# DC-Motor-DRV.net
KiCad netlist of a schematic drawn in Altium Designer
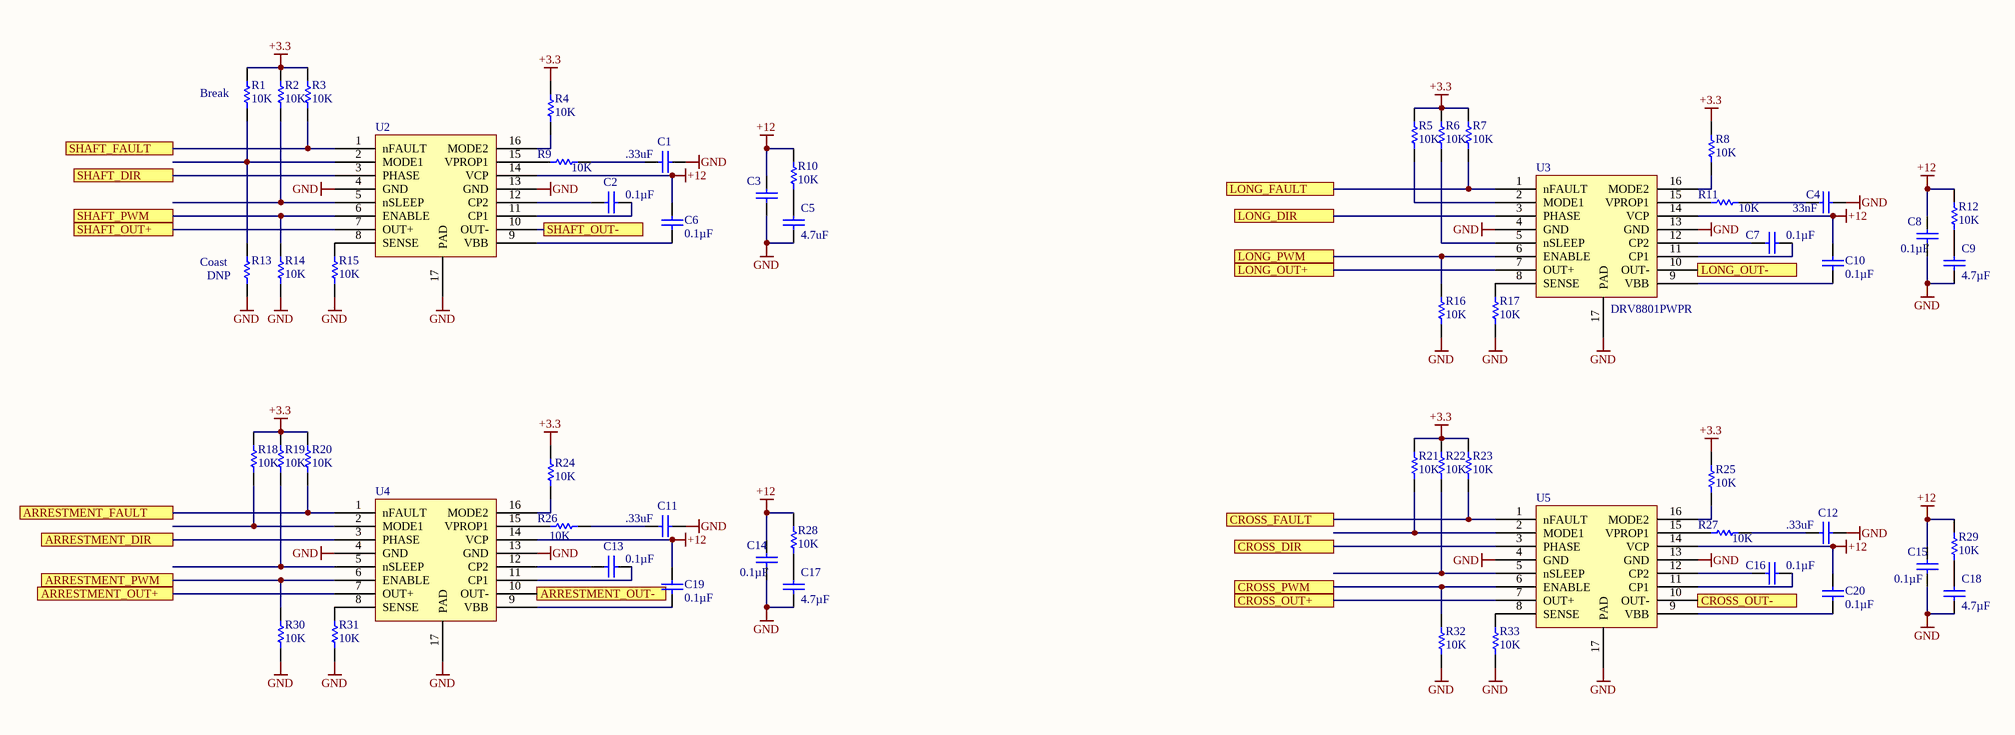
[diagram p0: DC-Motor-DRV.SchDoc]

(export (version "E")
  (design (tool "Eeschema 10.0.6"))
  (components
    (comp (ref "C1")
      (value ".33uF")
      (footprint "CAPC0805(2012)145_N")
      (description "CAP CER 0.1UF 25V X7R 0805")
      (fields
        (field (name "MANUFACTURER") "Wurth Electronics Inc.")
        (field (name "MANUFACTURER PART NUMBER") "885012207069")
      )
      (libsource (lib "Altium Content Vault") (part "CMP-1036-04795-1"))
    )
    (comp (ref "C2")
      (value "0.1uF")
      (footprint "CAPC0805(2012)145_N")
      (description "CAP CER 0.1UF 25V X7R 0805")
      (fields
        (field (name "MANUFACTURER") "Murata Electronics North America")
        (field (name "MANUFACTURER PART NUMBER") "GRM21BR71E104KA01L")
        (field (name "CAPACITANCE") "0.1µF")
      )
      (libsource (lib "Altium Content Vault") (part "CMP-1036-04795-1"))
    )
    (comp (ref "C3")
      (value "0.1uF")
      (footprint "CAPC0805(2012)145_N")
      (description "CAP CER 0.1UF 25V X7R 0805")
      (fields
        (field (name "MANUFACTURER") "Murata Electronics North America")
        (field (name "MANUFACTURER PART NUMBER") "GRM21BR71E104KA01L")
      )
      (libsource (lib "Altium Content Vault") (part "CMP-1036-04795-1"))
    )
    (comp (ref "C4")
      (value "33nF")
      (footprint "CAPC0402(1005)60_L")
      (description "CAP CER 33UF 10V X7R 0402")
      (fields
        (field (name "MANUFACTURER") "Murata Electronics North America")
        (field (name "MANUFACTURER PART NUMBER") "GRM155R71A104KA01D")
      )
      (libsource (lib "Altium Content Vault") (part "CMP-1034-00252-1"))
    )
    (comp (ref "C5")
      (value "4.7uF")
      (footprint "CAPC0805(2012)145_N")
      (description "CAP CER 4.7UF 25V 10% X7R 0805")
      (fields
        (field (name "MANUFACTURER") "Murata Electronics North America")
        (field (name "MANUFACTURER PART NUMBER") "GRM21BR71E104KA01L")
      )
      (libsource (lib "Altium Content Vault") (part "CMP-1036-04795-1"))
    )
    (comp (ref "C6")
      (value "0.1uF")
      (footprint "CAPC0805(2012)145_N")
      (description "CAP CER 0.1UF 25V X7R 0805")
      (fields
        (field (name "MANUFACTURER") "Murata Electronics North America")
        (field (name "MANUFACTURER PART NUMBER") "GRM21BR71E104KA01L")
        (field (name "CAPACITANCE") "0.1µF")
      )
      (libsource (lib "Altium Content Vault") (part "CMP-1036-04795-1"))
    )
    (comp (ref "C7")
      (value "0.1uF")
      (footprint "CAPC0805(2012)145_N")
      (description "CAP CER 0.1UF 25V X7R 0805")
      (fields
        (field (name "MANUFACTURER") "Murata Electronics North America")
        (field (name "MANUFACTURER PART NUMBER") "GRM21BR71E104KA01L")
        (field (name "CAPACITANCE") "0.1µF")
      )
      (libsource (lib "Altium Content Vault") (part "CMP-1036-04795-1"))
    )
    (comp (ref "C8")
      (value ".1uF")
      (footprint "CAPC0805(2012)145_N")
      (description "CAP CER 0.1UF 25V X7R 0805")
      (fields
        (field (name "MANUFACTURER") "Murata Electronics North America")
        (field (name "MANUFACTURER PART NUMBER") "GRM21BR71E104KA01L")
        (field (name "CAPACITANCE") "0.1µF")
      )
      (libsource (lib "Altium Content Vault") (part "CMP-1036-04795-1"))
    )
    (comp (ref "C9")
      (value "4.7uF")
      (footprint "CAPC0805(2012)145_N")
      (description "CAP CER 4.7UF 25V X7R 0805")
      (fields
        (field (name "MANUFACTURER") "Murata Electronics North America")
        (field (name "MANUFACTURER PART NUMBER") "GRM21BR71E104KA01L")
        (field (name "CAPACITANCE") "4.7µF")
      )
      (libsource (lib "Altium Content Vault") (part "CMP-1036-04795-1"))
    )
    (comp (ref "C10")
      (value ".1uF")
      (footprint "CAPC0805(2012)145_N")
      (description "CAP CER 0.1UF 25V X7R 0805")
      (fields
        (field (name "MANUFACTURER") "Murata Electronics North America")
        (field (name "MANUFACTURER PART NUMBER") "GRM21BR71E104KA01L")
        (field (name "CAPACITANCE") "0.1µF")
      )
      (libsource (lib "Altium Content Vault") (part "CMP-1036-04795-1"))
    )
    (comp (ref "C11")
      (value ".33uF")
      (footprint "CAPC0805(2012)145_N")
      (description "CAP CER 0.1UF 25V X7R 0805")
      (fields
        (field (name "MANUFACTURER") "Wurth Electronics Inc.")
        (field (name "MANUFACTURER PART NUMBER") "885012207069")
      )
      (libsource (lib "Altium Content Vault") (part "CMP-1036-04795-1"))
    )
    (comp (ref "C12")
      (value ".33uF")
      (footprint "CAPC0805(2012)145_N")
      (description "CAP CER 0.1UF 25V X7R 0805")
      (fields
        (field (name "MANUFACTURER") "Wurth Electronics Inc.")
        (field (name "MANUFACTURER PART NUMBER") "885012207069")
      )
      (libsource (lib "Altium Content Vault") (part "CMP-1036-04795-1"))
    )
    (comp (ref "C13")
      (value "CAP CER 0.1UF 25V X7R 0805")
      (footprint "CAPC0805(2012)145_N")
      (fields
        (field (name "MANUFACTURER") "Murata Electronics North America")
        (field (name "MANUFACTURER PART NUMBER") "GRM21BR71E104KA01L")
        (field (name "CAPACITANCE") "0.1µF")
        (field (name "TOLERANCE") "±10%")
      )
      (libsource (lib "Altium Content Vault") (part "CMP-1036-04795-1"))
    )
    (comp (ref "C14")
      (value "CAP CER 0.1UF 25V X7R 0805")
      (footprint "CAPC0805(2012)145_N")
      (fields
        (field (name "MANUFACTURER") "Murata Electronics North America")
        (field (name "MANUFACTURER PART NUMBER") "GRM21BR71E104KA01L")
        (field (name "CAPACITANCE") "0.1µF")
        (field (name "TOLERANCE") "±10%")
      )
      (libsource (lib "Altium Content Vault") (part "CMP-1036-04795-1"))
    )
    (comp (ref "C15")
      (value "0.1uF")
      (footprint "CAPC0805(2012)145_N")
      (description "CAP CER 0.1UF 25V X7R 0805")
      (fields
        (field (name "MANUFACTURER") "Murata Electronics North America")
        (field (name "MANUFACTURER PART NUMBER") "GRM21BR71E104KA01L")
        (field (name "CAPACITANCE") "0.1µF")
      )
      (libsource (lib "Altium Content Vault") (part "CMP-1036-04795-1"))
    )
    (comp (ref "C16")
      (value "0.1uF")
      (footprint "CAPC0805(2012)145_N")
      (description "CAP CER 0.1UF 25V X7R 0805")
      (fields
        (field (name "MANUFACTURER") "Murata Electronics North America")
        (field (name "MANUFACTURER PART NUMBER") "GRM21BR71E104KA01L")
        (field (name "CAPACITANCE") "0.1µF")
      )
      (libsource (lib "Altium Content Vault") (part "CMP-1036-04795-1"))
    )
    (comp (ref "C17")
      (value "CAP CER 0.1UF 25V X7R 0805")
      (footprint "CAPC0805(2012)145_N")
      (description "CAP CER 0.47UF 25V X7R 0805")
      (fields
        (field (name "MANUFACTURER") "Murata Electronics North America")
        (field (name "MANUFACTURER PART NUMBER") "GRM21BR71E104KA01L")
        (field (name "CAPACITANCE") "4.7µF")
      )
      (libsource (lib "Altium Content Vault") (part "CMP-1036-04795-1"))
    )
    (comp (ref "C18")
      (value "4.7uF")
      (footprint "CAPC0805(2012)145_N")
      (description "CAP CER 4.7UF 25V X7R 0805")
      (fields
        (field (name "MANUFACTURER") "Murata Electronics North America")
        (field (name "MANUFACTURER PART NUMBER") "GRM21BR71E104KA01L")
        (field (name "CAPACITANCE") "4.7µF")
      )
      (libsource (lib "Altium Content Vault") (part "CMP-1036-04795-1"))
    )
    (comp (ref "C19")
      (value "CAP CER 0.1UF 25V X7R 0805")
      (footprint "CAPC0805(2012)145_N")
      (fields
        (field (name "MANUFACTURER") "Murata Electronics North America")
        (field (name "MANUFACTURER PART NUMBER") "GRM21BR71E104KA01L")
        (field (name "CAPACITANCE") "0.1µF")
        (field (name "TOLERANCE") "±10%")
      )
      (libsource (lib "Altium Content Vault") (part "CMP-1036-04795-1"))
    )
    (comp (ref "C20")
      (value "0.1uF")
      (footprint "CAPC0805(2012)145_N")
      (description "CAP CER 0.1UF 25V X7R 0805")
      (fields
        (field (name "MANUFACTURER") "Murata Electronics North America")
        (field (name "MANUFACTURER PART NUMBER") "GRM21BR71E104KA01L")
        (field (name "CAPACITANCE") "0.1µF")
      )
      (libsource (lib "Altium Content Vault") (part "CMP-1036-04795-1"))
    )
    (comp (ref "R1")
      (value "10K")
      (footprint "RESC0805(2012)_L")
      (description "RES SMD 10K OHM 1% 1/8W 0805")
      (fields
        (field (name "MANUFACTURER") "Vishay Dale")
        (field (name "MANUFACTURER PART NUMBER") "CRCW080510K0FKEA")
      )
      (libsource (lib "Altium Content Vault") (part "CMP-1013-00215-1"))
    )
    (comp (ref "R2")
      (value "10K")
      (footprint "RESC0805(2012)_L")
      (description "RES SMD 10K OHM 1% 1/8W 0805")
      (fields
        (field (name "MANUFACTURER") "Vishay Dale")
        (field (name "MANUFACTURER PART NUMBER") "CRCW080510K0FKEA")
      )
      (libsource (lib "Altium Content Vault") (part "CMP-1013-00215-1"))
    )
    (comp (ref "R3")
      (value "10K")
      (footprint "RESC0805(2012)_L")
      (description "RES SMD 10K OHM 1% 1/8W 0805")
      (fields
        (field (name "MANUFACTURER") "Vishay Dale")
        (field (name "MANUFACTURER PART NUMBER") "CRCW080510K0FKEA")
      )
      (libsource (lib "Altium Content Vault") (part "CMP-1013-00215-1"))
    )
    (comp (ref "R4")
      (value "10K")
      (footprint "RESC0805(2012)_L")
      (description "RES SMD 10K OHM 1% 1/8W 0805")
      (fields
        (field (name "MANUFACTURER") "Vishay Dale")
        (field (name "MANUFACTURER PART NUMBER") "CRCW080510K0FKEA")
      )
      (libsource (lib "Altium Content Vault") (part "CMP-1013-00215-1"))
    )
    (comp (ref "R5")
      (value "10K")
      (footprint "RESC0805(2012)_L")
      (description "RES SMD 10K OHM 1% 1/8W 0805")
      (fields
        (field (name "MANUFACTURER") "Vishay Dale")
        (field (name "MANUFACTURER PART NUMBER") "CRCW080510K0FKEA")
      )
      (libsource (lib "Altium Content Vault") (part "CMP-1013-00215-1"))
    )
    (comp (ref "R6")
      (value "10K")
      (footprint "RESC0805(2012)_L")
      (description "RES SMD 10K OHM 1% 1/8W 0805")
      (fields
        (field (name "MANUFACTURER") "Vishay Dale")
        (field (name "MANUFACTURER PART NUMBER") "CRCW080510K0FKEA")
      )
      (libsource (lib "Altium Content Vault") (part "CMP-1013-00215-1"))
    )
    (comp (ref "R7")
      (value "10K")
      (footprint "RESC0805(2012)_L")
      (description "RES SMD 10K OHM 1% 1/8W 0805")
      (fields
        (field (name "MANUFACTURER") "Vishay Dale")
        (field (name "MANUFACTURER PART NUMBER") "CRCW080510K0FKEA")
      )
      (libsource (lib "Altium Content Vault") (part "CMP-1013-00215-1"))
    )
    (comp (ref "R8")
      (value "10K")
      (footprint "RESC0805(2012)_L")
      (description "RES SMD 10K OHM 1% 1/8W 0805")
      (fields
        (field (name "MANUFACTURER") "Vishay Dale")
        (field (name "MANUFACTURER PART NUMBER") "CRCW080510K0FKEA")
      )
      (libsource (lib "Altium Content Vault") (part "CMP-1013-00215-1"))
    )
    (comp (ref "R9")
      (value "10K")
      (footprint "RESC0805(2012)_L")
      (description "RES SMD 10K OHM 1% 1/8W 0805")
      (fields
        (field (name "MANUFACTURER") "Vishay Dale")
        (field (name "MANUFACTURER PART NUMBER") "CRCW080510K0FKEA")
      )
      (libsource (lib "Altium Content Vault") (part "CMP-1013-00215-1"))
    )
    (comp (ref "R10")
      (value "10K")
      (footprint "RESC0805(2012)_L")
      (description "RES SMD 1R OHM 1% 1/8W 0805")
      (fields
        (field (name "MANUFACTURER") "Vishay Dale")
        (field (name "MANUFACTURER PART NUMBER") "CRCW080510K0FKEA")
      )
      (libsource (lib "Altium Content Vault") (part "CMP-1013-00215-1"))
    )
    (comp (ref "R11")
      (value "10K")
      (footprint "RESC0805(2012)_L")
      (description "RES SMD 10K OHM 1% 1/8W 0805")
      (fields
        (field (name "MANUFACTURER") "Vishay Dale")
        (field (name "MANUFACTURER PART NUMBER") "CRCW080510K0FKEA")
      )
      (libsource (lib "Altium Content Vault") (part "CMP-1013-00215-1"))
    )
    (comp (ref "R12")
      (value "10K")
      (footprint "RESC0805(2012)_L")
      (description "RES SMD 1R OHM 1% 1/8W 0805")
      (fields
        (field (name "MANUFACTURER") "Vishay Dale")
        (field (name "MANUFACTURER PART NUMBER") "CRCW080510K0FKEA")
      )
      (libsource (lib "Altium Content Vault") (part "CMP-1013-00215-1"))
    )
    (comp (ref "R13")
      (value "DNP")
      (footprint "RESC0805(2012)_L")
      (description "RES SMD 10K OHM 1% 1/8W 0805")
      (fields
        (field (name "MANUFACTURER") "Vishay Dale")
        (field (name "MANUFACTURER PART NUMBER") "CRCW080510K0FKEA")
      )
      (libsource (lib "Altium Content Vault") (part "CMP-1013-00215-1"))
    )
    (comp (ref "R14")
      (value "10K")
      (footprint "RESC0805(2012)_L")
      (description "RES SMD 10K OHM 1% 1/8W 0805")
      (fields
        (field (name "MANUFACTURER") "Vishay Dale")
        (field (name "MANUFACTURER PART NUMBER") "CRCW080510K0FKEA")
      )
      (libsource (lib "Altium Content Vault") (part "CMP-1013-00215-1"))
    )
    (comp (ref "R15")
      (value "10K")
      (footprint "RESC0805(2012)_L")
      (description "RES SMD 10K OHM 1% 1/8W 0805")
      (fields
        (field (name "MANUFACTURER") "Vishay Dale")
        (field (name "MANUFACTURER PART NUMBER") "CRCW080510K0FKEA")
      )
      (libsource (lib "Altium Content Vault") (part "CMP-1013-00215-1"))
    )
    (comp (ref "R16")
      (value "10K")
      (footprint "RESC0805(2012)_L")
      (description "RES SMD 10K OHM 1% 1/8W 0805")
      (fields
        (field (name "MANUFACTURER") "Vishay Dale")
        (field (name "MANUFACTURER PART NUMBER") "CRCW080510K0FKEA")
      )
      (libsource (lib "Altium Content Vault") (part "CMP-1013-00215-1"))
    )
    (comp (ref "R17")
      (value "10K")
      (footprint "RESC0805(2012)_L")
      (description "RES SMD 10K OHM 1% 1/8W 0805")
      (fields
        (field (name "MANUFACTURER") "Vishay Dale")
        (field (name "MANUFACTURER PART NUMBER") "CRCW080510K0FKEA")
      )
      (libsource (lib "Altium Content Vault") (part "CMP-1013-00215-1"))
    )
    (comp (ref "R18")
      (value "10K")
      (footprint "RESC0805(2012)_L")
      (description "RES SMD 10K OHM 1% 1/8W 0805")
      (fields
        (field (name "MANUFACTURER") "Vishay Dale")
        (field (name "MANUFACTURER PART NUMBER") "CRCW080510K0FKEA")
      )
      (libsource (lib "Altium Content Vault") (part "CMP-1013-00215-1"))
    )
    (comp (ref "R19")
      (value "10K")
      (footprint "RESC0805(2012)_L")
      (description "RES SMD 10K OHM 1% 1/8W 0805")
      (fields
        (field (name "MANUFACTURER") "Vishay Dale")
        (field (name "MANUFACTURER PART NUMBER") "CRCW080510K0FKEA")
      )
      (libsource (lib "Altium Content Vault") (part "CMP-1013-00215-1"))
    )
    (comp (ref "R20")
      (value "10K")
      (footprint "RESC0805(2012)_L")
      (description "RES SMD 10K OHM 1% 1/8W 0805")
      (fields
        (field (name "MANUFACTURER") "Vishay Dale")
        (field (name "MANUFACTURER PART NUMBER") "CRCW080510K0FKEA")
      )
      (libsource (lib "Altium Content Vault") (part "CMP-1013-00215-1"))
    )
    (comp (ref "R21")
      (value "10K")
      (footprint "RESC0805(2012)_L")
      (description "RES SMD 10K OHM 1% 1/8W 0805")
      (fields
        (field (name "MANUFACTURER") "Vishay Dale")
        (field (name "MANUFACTURER PART NUMBER") "CRCW080510K0FKEA")
      )
      (libsource (lib "Altium Content Vault") (part "CMP-1013-00215-1"))
    )
    (comp (ref "R22")
      (value "10K")
      (footprint "RESC0805(2012)_L")
      (description "RES SMD 10K OHM 1% 1/8W 0805")
      (fields
        (field (name "MANUFACTURER") "Vishay Dale")
        (field (name "MANUFACTURER PART NUMBER") "CRCW080510K0FKEA")
      )
      (libsource (lib "Altium Content Vault") (part "CMP-1013-00215-1"))
    )
    (comp (ref "R23")
      (value "10K")
      (footprint "RESC0805(2012)_L")
      (description "RES SMD 10K OHM 1% 1/8W 0805")
      (fields
        (field (name "MANUFACTURER") "Vishay Dale")
        (field (name "MANUFACTURER PART NUMBER") "CRCW080510K0FKEA")
      )
      (libsource (lib "Altium Content Vault") (part "CMP-1013-00215-1"))
    )
    (comp (ref "R24")
      (value "10K")
      (footprint "RESC0805(2012)_L")
      (description "RES SMD 10K OHM 1% 1/8W 0805")
      (fields
        (field (name "MANUFACTURER") "Vishay Dale")
        (field (name "MANUFACTURER PART NUMBER") "CRCW080510K0FKEA")
      )
      (libsource (lib "Altium Content Vault") (part "CMP-1013-00215-1"))
    )
    (comp (ref "R25")
      (value "10K")
      (footprint "RESC0805(2012)_L")
      (description "RES SMD 10K OHM 1% 1/8W 0805")
      (fields
        (field (name "MANUFACTURER") "Vishay Dale")
        (field (name "MANUFACTURER PART NUMBER") "CRCW080510K0FKEA")
      )
      (libsource (lib "Altium Content Vault") (part "CMP-1013-00215-1"))
    )
    (comp (ref "R26")
      (value "10K")
      (footprint "RESC0805(2012)_L")
      (description "RES SMD 10K OHM 1% 1/8W 0805")
      (fields
        (field (name "MANUFACTURER") "Vishay Dale")
        (field (name "MANUFACTURER PART NUMBER") "CRCW080510K0FKEA")
      )
      (libsource (lib "Altium Content Vault") (part "CMP-1013-00215-1"))
    )
    (comp (ref "R27")
      (value "10K")
      (footprint "RESC0805(2012)_L")
      (description "RES SMD 10K OHM 1% 1/8W 0805")
      (fields
        (field (name "MANUFACTURER") "Vishay Dale")
        (field (name "MANUFACTURER PART NUMBER") "CRCW080510K0FKEA")
      )
      (libsource (lib "Altium Content Vault") (part "CMP-1013-00215-1"))
    )
    (comp (ref "R28")
      (value "10K")
      (footprint "RESC0805(2012)_L")
      (description "RES SMD 1R OHM 1% 1/8W 0805")
      (fields
        (field (name "MANUFACTURER") "Vishay Dale")
        (field (name "MANUFACTURER PART NUMBER") "CRCW080510K0FKEA")
      )
      (libsource (lib "Altium Content Vault") (part "CMP-1013-00215-1"))
    )
    (comp (ref "R29")
      (value "10K")
      (footprint "RESC0805(2012)_L")
      (description "RES SMD 1R OHM 1% 1/8W 0805")
      (fields
        (field (name "MANUFACTURER") "Vishay Dale")
        (field (name "MANUFACTURER PART NUMBER") "CRCW080510K0FKEA")
      )
      (libsource (lib "Altium Content Vault") (part "CMP-1013-00215-1"))
    )
    (comp (ref "R30")
      (value "10K")
      (footprint "RESC0805(2012)_L")
      (description "RES SMD 10K OHM 1% 1/8W 0805")
      (fields
        (field (name "MANUFACTURER") "Vishay Dale")
        (field (name "MANUFACTURER PART NUMBER") "CRCW080510K0FKEA")
      )
      (libsource (lib "Altium Content Vault") (part "CMP-1013-00215-1"))
    )
    (comp (ref "R31")
      (value "10K")
      (footprint "RESC0805(2012)_L")
      (description "RES SMD 10K OHM 1% 1/8W 0805")
      (fields
        (field (name "MANUFACTURER") "Vishay Dale")
        (field (name "MANUFACTURER PART NUMBER") "CRCW080510K0FKEA")
      )
      (libsource (lib "Altium Content Vault") (part "CMP-1013-00215-1"))
    )
    (comp (ref "R32")
      (value "10K")
      (footprint "RESC0805(2012)_L")
      (description "RES SMD 10K OHM 1% 1/8W 0805")
      (fields
        (field (name "MANUFACTURER") "Vishay Dale")
        (field (name "MANUFACTURER PART NUMBER") "CRCW080510K0FKEA")
      )
      (libsource (lib "Altium Content Vault") (part "CMP-1013-00215-1"))
    )
    (comp (ref "R33")
      (value "10K")
      (footprint "RESC0805(2012)_L")
      (description "RES SMD 10K OHM 1% 1/8W 0805")
      (fields
        (field (name "MANUFACTURER") "Vishay Dale")
        (field (name "MANUFACTURER PART NUMBER") "CRCW080510K0FKEA")
      )
      (libsource (lib "Altium Content Vault") (part "CMP-1013-00215-1"))
    )
    (comp (ref "U2")
      (value "DRV8801PWPR")
      (footprint "DRV8801PWPR")
      (description "IC MOTOR DRIVER PAR 16HTSSOP")
      (fields (field (name "MANUFACTURER") "Texas Instruments") (field (name "BASE PART NUMBER") "DRV8801"))
      (libsource (lib "ZLS_Schematic_lib") (part "DRV8801PWPR"))
    )
    (comp (ref "U3")
      (value "DRV8801PWPR")
      (footprint "DRV8801PWPR")
      (description "IC MOTOR DRIVER PAR 16HTSSOP")
      (fields (field (name "MANUFACTURER") "Texas Instruments") (field (name "BASE PART NUMBER") "DRV8801"))
      (libsource (lib "ZLS_Schematic_lib") (part "DRV8801PWPR"))
    )
    (comp (ref "U4")
      (value "DRV8801PWPR")
      (footprint "DRV8801PWPR")
      (description "IC MOTOR DRIVER PAR 16HTSSOP")
      (fields (field (name "MANUFACTURER") "Texas Instruments") (field (name "BASE PART NUMBER") "DRV8801"))
      (libsource (lib "ZLS_Schematic_lib") (part "DRV8801PWPR"))
    )
    (comp (ref "U5")
      (value "DRV8801PWPR")
      (footprint "DRV8801PWPR")
      (description "IC MOTOR DRIVER PAR 16HTSSOP")
      (fields (field (name "MANUFACTURER") "Texas Instruments") (field (name "BASE PART NUMBER") "DRV8801"))
      (libsource (lib "ZLS_Schematic_lib") (part "DRV8801PWPR"))
    )
  )
  (nets
    (net (code "1") (name "+3.3") (class "Default")
      (node (ref "R1") (pin "1") (pinfunction "1_1") (pintype "passive"))
      (node (ref "R18") (pin "1") (pinfunction "1_1") (pintype "passive"))
      (node (ref "R19") (pin "1") (pinfunction "1_1") (pintype "passive"))
      (node (ref "R2") (pin "1") (pinfunction "1_1") (pintype "passive"))
      (node (ref "R20") (pin "1") (pinfunction "1_1") (pintype "passive"))
      (node (ref "R21") (pin "1") (pinfunction "1_1") (pintype "passive"))
      (node (ref "R22") (pin "1") (pinfunction "1_1") (pintype "passive"))
      (node (ref "R23") (pin "1") (pinfunction "1_1") (pintype "passive"))
      (node (ref "R24") (pin "1") (pinfunction "1_1") (pintype "passive"))
      (node (ref "R25") (pin "1") (pinfunction "1_1") (pintype "passive"))
      (node (ref "R3") (pin "1") (pinfunction "1_1") (pintype "passive"))
      (node (ref "R4") (pin "1") (pinfunction "1_1") (pintype "passive"))
      (node (ref "R5") (pin "1") (pinfunction "1_1") (pintype "passive"))
      (node (ref "R6") (pin "1") (pinfunction "1_1") (pintype "passive"))
      (node (ref "R7") (pin "1") (pinfunction "1_1") (pintype "passive"))
      (node (ref "R8") (pin "1") (pinfunction "1_1") (pintype "passive"))
    )
    (net (code "2") (name "+12") (class "Default")
      (node (ref "C10") (pin "2") (pinfunction "2_2") (pintype "passive"))
      (node (ref "C14") (pin "1") (pinfunction "1_1") (pintype "passive"))
      (node (ref "C15") (pin "1") (pinfunction "1_1") (pintype "passive"))
      (node (ref "C19") (pin "2") (pinfunction "2_2") (pintype "passive"))
      (node (ref "C20") (pin "2") (pinfunction "2_2") (pintype "passive"))
      (node (ref "C3") (pin "1") (pinfunction "1_1") (pintype "passive"))
      (node (ref "C6") (pin "2") (pinfunction "2_2") (pintype "passive"))
      (node (ref "C8") (pin "1") (pinfunction "1_1") (pintype "passive"))
      (node (ref "R10") (pin "1") (pinfunction "1_1") (pintype "passive"))
      (node (ref "R12") (pin "1") (pinfunction "1_1") (pintype "passive"))
      (node (ref "R28") (pin "1") (pinfunction "1_1") (pintype "passive"))
      (node (ref "R29") (pin "1") (pinfunction "1_1") (pintype "passive"))
      (node (ref "U2") (pin "14") (pinfunction "VCP_14") (pintype "passive"))
      (node (ref "U3") (pin "14") (pinfunction "VCP_14") (pintype "passive"))
      (node (ref "U4") (pin "14") (pinfunction "VCP_14") (pintype "passive"))
      (node (ref "U5") (pin "14") (pinfunction "VCP_14") (pintype "passive"))
    )
    (net (code "3") (name "/ARRESTMENT_DIR") (class "Default")
      (node (ref "U4") (pin "3") (pinfunction "PHASE_3") (pintype "passive"))
    )
    (net (code "4") (name "/ARRESTMENT_FAULT") (class "Default")
      (node (ref "R20") (pin "2") (pinfunction "2_2") (pintype "passive"))
      (node (ref "U4") (pin "1") (pinfunction "nFAULT_1") (pintype "passive"))
    )
    (net (code "5") (name "/ARRESTMENT_OUT+") (class "Default")
      (node (ref "U4") (pin "7") (pinfunction "OUT+_7") (pintype "passive"))
    )
    (net (code "6") (name "/ARRESTMENT_OUT-") (class "Default")
      (node (ref "U4") (pin "10") (pinfunction "OUT-_10") (pintype "passive"))
    )
    (net (code "7") (name "/ARRESTMENT_PWM") (class "Default")
      (node (ref "R30") (pin "1") (pinfunction "1_1") (pintype "passive"))
      (node (ref "U4") (pin "6") (pinfunction "ENABLE_6") (pintype "passive"))
    )
    (net (code "8") (name "/CROSS_DIR") (class "Default")
      (node (ref "U5") (pin "3") (pinfunction "PHASE_3") (pintype "passive"))
    )
    (net (code "9") (name "/CROSS_FAULT") (class "Default")
      (node (ref "R23") (pin "2") (pinfunction "2_2") (pintype "passive"))
      (node (ref "U5") (pin "1") (pinfunction "nFAULT_1") (pintype "passive"))
    )
    (net (code "10") (name "/CROSS_OUT+") (class "Default")
      (node (ref "U5") (pin "7") (pinfunction "OUT+_7") (pintype "passive"))
    )
    (net (code "11") (name "/CROSS_OUT-") (class "Default")
      (node (ref "U5") (pin "10") (pinfunction "OUT-_10") (pintype "passive"))
    )
    (net (code "12") (name "/CROSS_PWM") (class "Default")
      (node (ref "R32") (pin "1") (pinfunction "1_1") (pintype "passive"))
      (node (ref "U5") (pin "6") (pinfunction "ENABLE_6") (pintype "passive"))
    )
    (net (code "13") (name "/LONG_DIR") (class "Default")
      (node (ref "U3") (pin "3") (pinfunction "PHASE_3") (pintype "passive"))
    )
    (net (code "14") (name "/LONG_FAULT") (class "Default")
      (node (ref "R7") (pin "2") (pinfunction "2_2") (pintype "passive"))
      (node (ref "U3") (pin "1") (pinfunction "nFAULT_1") (pintype "passive"))
    )
    (net (code "15") (name "/LONG_OUT+") (class "Default")
      (node (ref "U3") (pin "7") (pinfunction "OUT+_7") (pintype "passive"))
    )
    (net (code "16") (name "/LONG_OUT-") (class "Default")
      (node (ref "U3") (pin "10") (pinfunction "OUT-_10") (pintype "passive"))
    )
    (net (code "17") (name "/LONG_PWM") (class "Default")
      (node (ref "R16") (pin "1") (pinfunction "1_1") (pintype "passive"))
      (node (ref "U3") (pin "6") (pinfunction "ENABLE_6") (pintype "passive"))
    )
    (net (code "18") (name "/SHAFT_DIR") (class "Default")
      (node (ref "U2") (pin "3") (pinfunction "PHASE_3") (pintype "passive"))
    )
    (net (code "19") (name "/SHAFT_FAULT") (class "Default")
      (node (ref "R3") (pin "2") (pinfunction "2_2") (pintype "passive"))
      (node (ref "U2") (pin "1") (pinfunction "nFAULT_1") (pintype "passive"))
    )
    (net (code "20") (name "/SHAFT_OUT+") (class "Default")
      (node (ref "U2") (pin "7") (pinfunction "OUT+_7") (pintype "passive"))
    )
    (net (code "21") (name "/SHAFT_OUT-") (class "Default")
      (node (ref "U2") (pin "10") (pinfunction "OUT-_10") (pintype "passive"))
    )
    (net (code "22") (name "/SHAFT_PWM") (class "Default")
      (node (ref "R14") (pin "1") (pinfunction "1_1") (pintype "passive"))
      (node (ref "U2") (pin "6") (pinfunction "ENABLE_6") (pintype "passive"))
    )
    (net (code "23") (name "GND") (class "Default")
      (node (ref "C1") (pin "1") (pinfunction "1_1") (pintype "passive"))
      (node (ref "C11") (pin "1") (pinfunction "1_1") (pintype "passive"))
      (node (ref "C12") (pin "1") (pinfunction "1_1") (pintype "passive"))
      (node (ref "C14") (pin "2") (pinfunction "2_2") (pintype "passive"))
      (node (ref "C15") (pin "2") (pinfunction "2_2") (pintype "passive"))
      (node (ref "C17") (pin "2") (pinfunction "2_2") (pintype "passive"))
      (node (ref "C18") (pin "2") (pinfunction "2_2") (pintype "passive"))
      (node (ref "C3") (pin "2") (pinfunction "2_2") (pintype "passive"))
      (node (ref "C4") (pin "2") (pinfunction "2_2") (pintype "passive"))
      (node (ref "C5") (pin "2") (pinfunction "2_2") (pintype "passive"))
      (node (ref "C8") (pin "2") (pinfunction "2_2") (pintype "passive"))
      (node (ref "C9") (pin "2") (pinfunction "2_2") (pintype "passive"))
      (node (ref "R13") (pin "2") (pinfunction "2_2") (pintype "passive"))
      (node (ref "R14") (pin "2") (pinfunction "2_2") (pintype "passive"))
      (node (ref "R15") (pin "2") (pinfunction "2_2") (pintype "passive"))
      (node (ref "R16") (pin "2") (pinfunction "2_2") (pintype "passive"))
      (node (ref "R17") (pin "2") (pinfunction "2_2") (pintype "passive"))
      (node (ref "R30") (pin "2") (pinfunction "2_2") (pintype "passive"))
      (node (ref "R31") (pin "2") (pinfunction "2_2") (pintype "passive"))
      (node (ref "R32") (pin "2") (pinfunction "2_2") (pintype "passive"))
      (node (ref "R33") (pin "2") (pinfunction "2_2") (pintype "passive"))
      (node (ref "U2") (pin "13") (pinfunction "GND_13") (pintype "passive"))
      (node (ref "U2") (pin "17") (pinfunction "PAD_17") (pintype "passive"))
      (node (ref "U2") (pin "4") (pinfunction "GND_4") (pintype "passive"))
      (node (ref "U3") (pin "13") (pinfunction "GND_13") (pintype "passive"))
      (node (ref "U3") (pin "17") (pinfunction "PAD_17") (pintype "passive"))
      (node (ref "U3") (pin "4") (pinfunction "GND_4") (pintype "passive"))
      (node (ref "U4") (pin "13") (pinfunction "GND_13") (pintype "passive"))
      (node (ref "U4") (pin "17") (pinfunction "PAD_17") (pintype "passive"))
      (node (ref "U4") (pin "4") (pinfunction "GND_4") (pintype "passive"))
      (node (ref "U5") (pin "13") (pinfunction "GND_13") (pintype "passive"))
      (node (ref "U5") (pin "17") (pinfunction "PAD_17") (pintype "passive"))
      (node (ref "U5") (pin "4") (pinfunction "GND_4") (pintype "passive"))
    )
    (net (code "24") (name "Net-(C1-Pad2)") (class "Default")
      (node (ref "C1") (pin "2") (pinfunction "2_2") (pintype "passive"))
      (node (ref "R9") (pin "1") (pinfunction "1_1") (pintype "passive"))
    )
    (net (code "25") (name "Net-(C4-Pad1)") (class "Default")
      (node (ref "C4") (pin "1") (pinfunction "1_1") (pintype "passive"))
      (node (ref "R11") (pin "1") (pinfunction "1_1") (pintype "passive"))
    )
    (net (code "26") (name "Net-(C5-Pad1)") (class "Default")
      (node (ref "C5") (pin "1") (pinfunction "1_1") (pintype "passive"))
      (node (ref "R10") (pin "2") (pinfunction "2_2") (pintype "passive"))
    )
    (net (code "27") (name "Net-(C9-Pad1)") (class "Default")
      (node (ref "C9") (pin "1") (pinfunction "1_1") (pintype "passive"))
      (node (ref "R12") (pin "2") (pinfunction "2_2") (pintype "passive"))
    )
    (net (code "28") (name "Net-(C11-Pad2)") (class "Default")
      (node (ref "C11") (pin "2") (pinfunction "2_2") (pintype "passive"))
      (node (ref "R26") (pin "1") (pinfunction "1_1") (pintype "passive"))
    )
    (net (code "29") (name "Net-(C12-Pad2)") (class "Default")
      (node (ref "C12") (pin "2") (pinfunction "2_2") (pintype "passive"))
      (node (ref "R27") (pin "1") (pinfunction "1_1") (pintype "passive"))
    )
    (net (code "30") (name "Net-(C17-Pad1)") (class "Default")
      (node (ref "C17") (pin "1") (pinfunction "1_1") (pintype "passive"))
      (node (ref "R28") (pin "2") (pinfunction "2_2") (pintype "passive"))
    )
    (net (code "31") (name "Net-(C18-Pad1)") (class "Default")
      (node (ref "C18") (pin "1") (pinfunction "1_1") (pintype "passive"))
      (node (ref "R29") (pin "2") (pinfunction "2_2") (pintype "passive"))
    )
    (net (code "32") (name "Net-(U2-CP1)") (class "Default")
      (node (ref "C2") (pin "2") (pinfunction "2_2") (pintype "passive"))
      (node (ref "U2") (pin "11") (pinfunction "CP1_11") (pintype "passive"))
    )
    (net (code "33") (name "Net-(U2-CP2)") (class "Default")
      (node (ref "C2") (pin "1") (pinfunction "1_1") (pintype "passive"))
      (node (ref "U2") (pin "12") (pinfunction "CP2_12") (pintype "passive"))
    )
    (net (code "34") (name "Net-(U2-MODE1)") (class "Default")
      (node (ref "R1") (pin "2") (pinfunction "2_2") (pintype "passive"))
      (node (ref "R13") (pin "1") (pinfunction "1_1") (pintype "passive"))
      (node (ref "U2") (pin "2") (pinfunction "MODE1_2") (pintype "passive"))
    )
    (net (code "35") (name "Net-(U2-MODE2)") (class "Default")
      (node (ref "R4") (pin "2") (pinfunction "2_2") (pintype "passive"))
      (node (ref "U2") (pin "16") (pinfunction "MODE2_16") (pintype "passive"))
    )
    (net (code "36") (name "Net-(U2-SENSE)") (class "Default")
      (node (ref "R15") (pin "1") (pinfunction "1_1") (pintype "passive"))
      (node (ref "U2") (pin "8") (pinfunction "SENSE_8") (pintype "passive"))
    )
    (net (code "37") (name "Net-(U2-VBB)") (class "Default")
      (node (ref "C6") (pin "1") (pinfunction "1_1") (pintype "passive"))
      (node (ref "U2") (pin "9") (pinfunction "VBB_9") (pintype "passive"))
    )
    (net (code "38") (name "Net-(U2-VPROP1)") (class "Default")
      (node (ref "R9") (pin "2") (pinfunction "2_2") (pintype "passive"))
      (node (ref "U2") (pin "15") (pinfunction "VPROP1_15") (pintype "passive"))
    )
    (net (code "39") (name "Net-(U2-nSLEEP)") (class "Default")
      (node (ref "R2") (pin "2") (pinfunction "2_2") (pintype "passive"))
      (node (ref "U2") (pin "5") (pinfunction "nSLEEP_5") (pintype "passive"))
    )
    (net (code "40") (name "Net-(U3-CP1)") (class "Default")
      (node (ref "C7") (pin "2") (pinfunction "2_2") (pintype "passive"))
      (node (ref "U3") (pin "11") (pinfunction "CP1_11") (pintype "passive"))
    )
    (net (code "41") (name "Net-(U3-CP2)") (class "Default")
      (node (ref "C7") (pin "1") (pinfunction "1_1") (pintype "passive"))
      (node (ref "U3") (pin "12") (pinfunction "CP2_12") (pintype "passive"))
    )
    (net (code "42") (name "Net-(U3-MODE1)") (class "Default")
      (node (ref "R5") (pin "2") (pinfunction "2_2") (pintype "passive"))
      (node (ref "U3") (pin "2") (pinfunction "MODE1_2") (pintype "passive"))
    )
    (net (code "43") (name "Net-(U3-MODE2)") (class "Default")
      (node (ref "R8") (pin "2") (pinfunction "2_2") (pintype "passive"))
      (node (ref "U3") (pin "16") (pinfunction "MODE2_16") (pintype "passive"))
    )
    (net (code "44") (name "Net-(U3-SENSE)") (class "Default")
      (node (ref "R17") (pin "1") (pinfunction "1_1") (pintype "passive"))
      (node (ref "U3") (pin "8") (pinfunction "SENSE_8") (pintype "passive"))
    )
    (net (code "45") (name "Net-(U3-VBB)") (class "Default")
      (node (ref "C10") (pin "1") (pinfunction "1_1") (pintype "passive"))
      (node (ref "U3") (pin "9") (pinfunction "VBB_9") (pintype "passive"))
    )
    (net (code "46") (name "Net-(U3-VPROP1)") (class "Default")
      (node (ref "R11") (pin "2") (pinfunction "2_2") (pintype "passive"))
      (node (ref "U3") (pin "15") (pinfunction "VPROP1_15") (pintype "passive"))
    )
    (net (code "47") (name "Net-(U3-nSLEEP)") (class "Default")
      (node (ref "R6") (pin "2") (pinfunction "2_2") (pintype "passive"))
      (node (ref "U3") (pin "5") (pinfunction "nSLEEP_5") (pintype "passive"))
    )
    (net (code "48") (name "Net-(U4-CP1)") (class "Default")
      (node (ref "C13") (pin "2") (pinfunction "2_2") (pintype "passive"))
      (node (ref "U4") (pin "11") (pinfunction "CP1_11") (pintype "passive"))
    )
    (net (code "49") (name "Net-(U4-CP2)") (class "Default")
      (node (ref "C13") (pin "1") (pinfunction "1_1") (pintype "passive"))
      (node (ref "U4") (pin "12") (pinfunction "CP2_12") (pintype "passive"))
    )
    (net (code "50") (name "Net-(U4-MODE1)") (class "Default")
      (node (ref "R18") (pin "2") (pinfunction "2_2") (pintype "passive"))
      (node (ref "U4") (pin "2") (pinfunction "MODE1_2") (pintype "passive"))
    )
    (net (code "51") (name "Net-(U4-MODE2)") (class "Default")
      (node (ref "R24") (pin "2") (pinfunction "2_2") (pintype "passive"))
      (node (ref "U4") (pin "16") (pinfunction "MODE2_16") (pintype "passive"))
    )
    (net (code "52") (name "Net-(U4-SENSE)") (class "Default")
      (node (ref "R31") (pin "1") (pinfunction "1_1") (pintype "passive"))
      (node (ref "U4") (pin "8") (pinfunction "SENSE_8") (pintype "passive"))
    )
    (net (code "53") (name "Net-(U4-VBB)") (class "Default")
      (node (ref "C19") (pin "1") (pinfunction "1_1") (pintype "passive"))
      (node (ref "U4") (pin "9") (pinfunction "VBB_9") (pintype "passive"))
    )
    (net (code "54") (name "Net-(U4-VPROP1)") (class "Default")
      (node (ref "R26") (pin "2") (pinfunction "2_2") (pintype "passive"))
      (node (ref "U4") (pin "15") (pinfunction "VPROP1_15") (pintype "passive"))
    )
    (net (code "55") (name "Net-(U4-nSLEEP)") (class "Default")
      (node (ref "R19") (pin "2") (pinfunction "2_2") (pintype "passive"))
      (node (ref "U4") (pin "5") (pinfunction "nSLEEP_5") (pintype "passive"))
    )
    (net (code "56") (name "Net-(U5-CP1)") (class "Default")
      (node (ref "C16") (pin "2") (pinfunction "2_2") (pintype "passive"))
      (node (ref "U5") (pin "11") (pinfunction "CP1_11") (pintype "passive"))
    )
    (net (code "57") (name "Net-(U5-CP2)") (class "Default")
      (node (ref "C16") (pin "1") (pinfunction "1_1") (pintype "passive"))
      (node (ref "U5") (pin "12") (pinfunction "CP2_12") (pintype "passive"))
    )
    (net (code "58") (name "Net-(U5-MODE1)") (class "Default")
      (node (ref "R21") (pin "2") (pinfunction "2_2") (pintype "passive"))
      (node (ref "U5") (pin "2") (pinfunction "MODE1_2") (pintype "passive"))
    )
    (net (code "59") (name "Net-(U5-MODE2)") (class "Default")
      (node (ref "R25") (pin "2") (pinfunction "2_2") (pintype "passive"))
      (node (ref "U5") (pin "16") (pinfunction "MODE2_16") (pintype "passive"))
    )
    (net (code "60") (name "Net-(U5-SENSE)") (class "Default")
      (node (ref "R33") (pin "1") (pinfunction "1_1") (pintype "passive"))
      (node (ref "U5") (pin "8") (pinfunction "SENSE_8") (pintype "passive"))
    )
    (net (code "61") (name "Net-(U5-VBB)") (class "Default")
      (node (ref "C20") (pin "1") (pinfunction "1_1") (pintype "passive"))
      (node (ref "U5") (pin "9") (pinfunction "VBB_9") (pintype "passive"))
    )
    (net (code "62") (name "Net-(U5-VPROP1)") (class "Default")
      (node (ref "R27") (pin "2") (pinfunction "2_2") (pintype "passive"))
      (node (ref "U5") (pin "15") (pinfunction "VPROP1_15") (pintype "passive"))
    )
    (net (code "63") (name "Net-(U5-nSLEEP)") (class "Default")
      (node (ref "R22") (pin "2") (pinfunction "2_2") (pintype "passive"))
      (node (ref "U5") (pin "5") (pinfunction "nSLEEP_5") (pintype "passive"))
    )
  )
)
